# D1-Mini_Adapter_V4.net
KiCad netlist of a schematic drawn in EAGLE
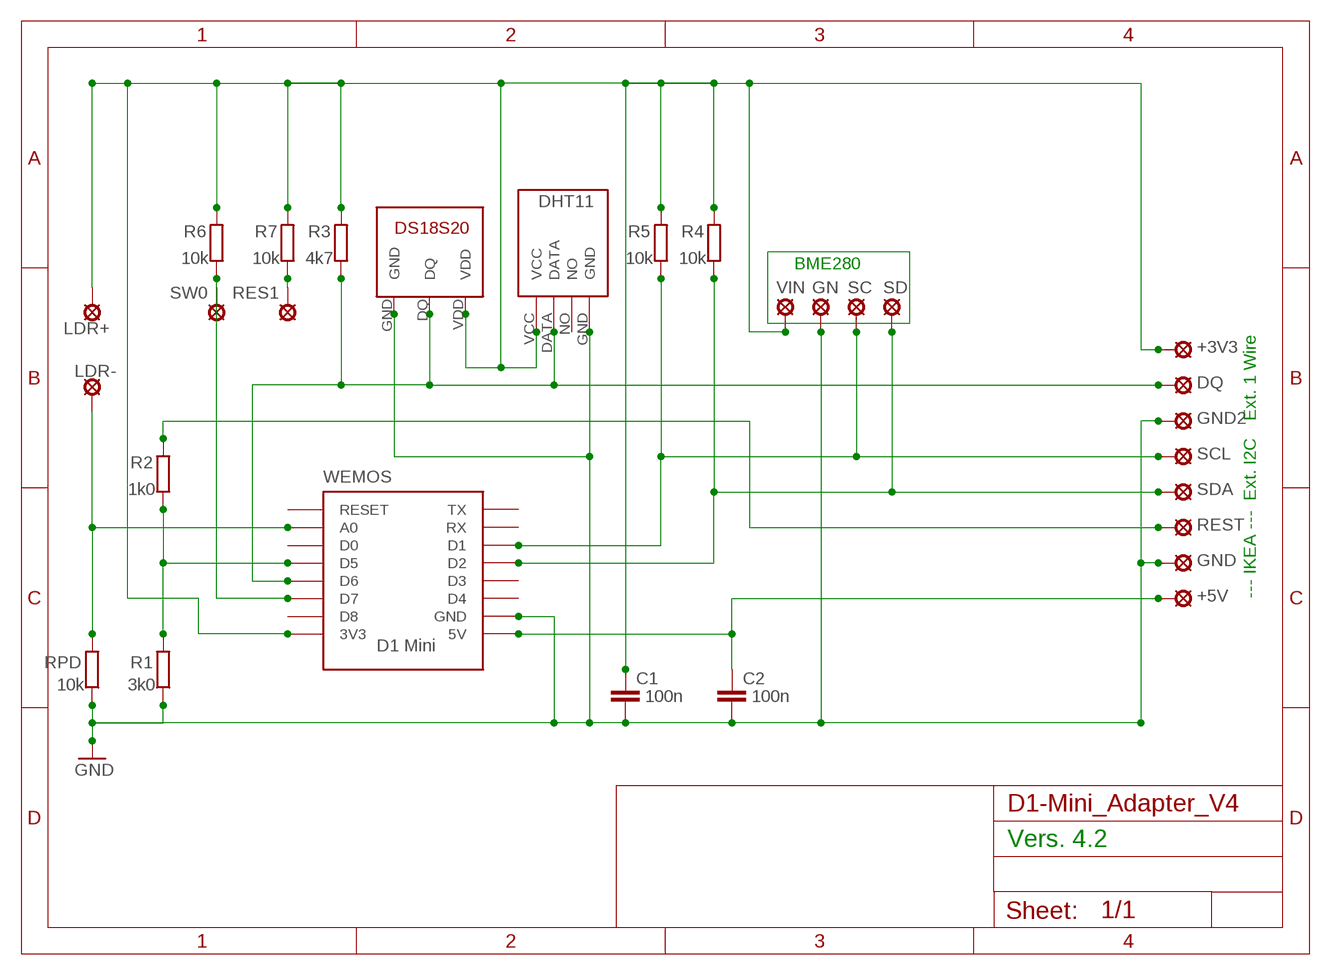
[diagram p0: schematic, sheet 1]

(export (version "E")
  (design (tool "Eeschema 10.0.6"))
  (components
    (comp (ref "+3V3")
      (value "SE13")
      (footprint "eagle-import:SE13")
      (libsource (lib "eagle-import") (part "SE13"))
    )
    (comp (ref "+5V")
      (value "SE13")
      (footprint "eagle-import:SE13")
      (libsource (lib "eagle-import") (part "SE13"))
    )
    (comp (ref "C1")
      (value "100n")
      (footprint "eagle-import:C025_050-045X075")
      (libsource (lib "eagle-import") (part "C-EU025_050-045X075"))
    )
    (comp (ref "C2")
      (value "100n")
      (footprint "eagle-import:C025_050-045X075")
      (libsource (lib "eagle-import") (part "C-EU025_050-045X075"))
    )
    (comp (ref "DQ")
      (value "SE13")
      (footprint "eagle-import:SE13")
      (libsource (lib "eagle-import") (part "SE13"))
    )
    (comp (ref "DS1820")
      (value "DS18S20")
      (footprint "eagle-import:DS18S20-PACKAGE")
      (libsource (lib "eagle-import") (part "DS18S20"))
    )
    (comp (ref "GN")
      (value "SE13")
      (footprint "eagle-import:SE13")
      (libsource (lib "eagle-import") (part "SE13"))
    )
    (comp (ref "GND")
      (value "SE13")
      (footprint "eagle-import:SE13")
      (libsource (lib "eagle-import") (part "SE13"))
    )
    (comp (ref "GND2")
      (value "SE13")
      (footprint "eagle-import:SE13")
      (libsource (lib "eagle-import") (part "SE13"))
    )
    (comp (ref "LDR+")
      (value "SE13")
      (footprint "eagle-import:SE13")
      (libsource (lib "eagle-import") (part "SE13"))
    )
    (comp (ref "LDR-")
      (value "SE13")
      (footprint "eagle-import:SE13")
      (libsource (lib "eagle-import") (part "SE13"))
    )
    (comp (ref "R1")
      (value "3k0")
      (footprint "eagle-import:0207_10")
      (libsource (lib "eagle-import") (part "R-EU_0207/10"))
    )
    (comp (ref "R2")
      (value "1k0")
      (footprint "eagle-import:0207_10")
      (libsource (lib "eagle-import") (part "R-EU_0207/10"))
    )
    (comp (ref "R3")
      (value "4k7")
      (footprint "eagle-import:0207_10")
      (libsource (lib "eagle-import") (part "R-EU_0207/10"))
    )
    (comp (ref "R4")
      (value "10k")
      (footprint "eagle-import:0207_10")
      (libsource (lib "eagle-import") (part "R-EU_0207/10"))
    )
    (comp (ref "R5")
      (value "10k")
      (footprint "eagle-import:0207_10")
      (libsource (lib "eagle-import") (part "R-EU_0207/10"))
    )
    (comp (ref "R6")
      (value "10k")
      (footprint "eagle-import:0207_10")
      (libsource (lib "eagle-import") (part "R-EU_0207/10"))
    )
    (comp (ref "R7")
      (value "10k")
      (footprint "eagle-import:0207_10")
      (libsource (lib "eagle-import") (part "R-EU_0207/10"))
    )
    (comp (ref "RES1")
      (value "SE13")
      (footprint "eagle-import:SE13")
      (libsource (lib "eagle-import") (part "SE13"))
    )
    (comp (ref "REST")
      (value "SE13")
      (footprint "eagle-import:SE13")
      (libsource (lib "eagle-import") (part "SE13"))
    )
    (comp (ref "RPD")
      (value "10k")
      (footprint "eagle-import:0207_10")
      (libsource (lib "eagle-import") (part "R-EU_0207/10"))
    )
    (comp (ref "SC")
      (value "SE13")
      (footprint "eagle-import:SE13")
      (libsource (lib "eagle-import") (part "SE13"))
    )
    (comp (ref "SCL")
      (value "SE13")
      (footprint "eagle-import:SE13")
      (libsource (lib "eagle-import") (part "SE13"))
    )
    (comp (ref "SD")
      (value "SE13")
      (footprint "eagle-import:SE13")
      (libsource (lib "eagle-import") (part "SE13"))
    )
    (comp (ref "SDA")
      (value "SE13")
      (footprint "eagle-import:SE13")
      (libsource (lib "eagle-import") (part "SE13"))
    )
    (comp (ref "SW0")
      (value "SE13")
      (footprint "eagle-import:SE13")
      (libsource (lib "eagle-import") (part "SE13"))
    )
    (comp (ref "U$1")
      (value "DHT11-PION.")
      (footprint "eagle-import:DHT11-PION.")
      (libsource (lib "eagle-import") (part "DHT11-PION."))
    )
    (comp (ref "VIN")
      (value "LSP13")
      (footprint "eagle-import:LSP13")
      (libsource (lib "eagle-import") (part "LSP13"))
    )
    (comp (ref "WEMOS")
      (value "D1 Mini")
      (footprint "eagle-import:WEMOS-D1-MINI")
      (libsource (lib "eagle-import") (part "WEMOS-D1-MINI"))
    )
  )
  (nets
    (net (code "1") (name "GND") (class "Default")
      (node (ref "C1") (pin "2") (pinfunction "2_2") (pintype "passive"))
      (node (ref "C2") (pin "2") (pinfunction "2_2") (pintype "passive"))
      (node (ref "DS1820") (pin "GND") (pinfunction "GND_GND") (pintype "power_in"))
      (node (ref "GN") (pin "MP") (pinfunction "MP_MP") (pintype "passive"))
      (node (ref "GND") (pin "MP") (pinfunction "MP_MP") (pintype "passive"))
      (node (ref "GND2") (pin "MP") (pinfunction "MP_MP") (pintype "passive"))
      (node (ref "R1") (pin "1") (pinfunction "1_1") (pintype "passive"))
      (node (ref "RPD") (pin "1") (pinfunction "1_1") (pintype "passive"))
      (node (ref "U$1") (pin "GND") (pinfunction "GND_GND") (pintype "bidirectional"))
      (node (ref "WEMOS") (pin "GND") (pinfunction "GND_GND") (pintype "bidirectional"))
    )
    (net (code "2") (name "Net-(+3V3-PadMP)") (class "Default")
      (node (ref "+3V3") (pin "MP") (pinfunction "MP_MP") (pintype "passive"))
      (node (ref "C1") (pin "1") (pinfunction "1_1") (pintype "passive"))
      (node (ref "DS1820") (pin "VDD") (pinfunction "VDD_VDD") (pintype "power_in"))
      (node (ref "LDR+") (pin "MP") (pinfunction "MP_MP") (pintype "passive"))
      (node (ref "R3") (pin "2") (pinfunction "2_2") (pintype "passive"))
      (node (ref "R4") (pin "2") (pinfunction "2_2") (pintype "passive"))
      (node (ref "R5") (pin "2") (pinfunction "2_2") (pintype "passive"))
      (node (ref "R6") (pin "2") (pinfunction "2_2") (pintype "passive"))
      (node (ref "R7") (pin "2") (pinfunction "2_2") (pintype "passive"))
      (node (ref "U$1") (pin "VCC") (pinfunction "VCC_VCC") (pintype "bidirectional"))
      (node (ref "VIN") (pin "MP") (pinfunction "MP_MP") (pintype "passive"))
      (node (ref "WEMOS") (pin "3V3") (pinfunction "3V3_3V3") (pintype "bidirectional"))
    )
    (net (code "3") (name "Net-(+5V-PadMP)") (class "Default")
      (node (ref "+5V") (pin "MP") (pinfunction "MP_MP") (pintype "passive"))
      (node (ref "C2") (pin "1") (pinfunction "1_1") (pintype "passive"))
      (node (ref "WEMOS") (pin "5V") (pinfunction "5V_5V") (pintype "bidirectional"))
    )
    (net (code "4") (name "Net-(DQ-PadMP)") (class "Default")
      (node (ref "DQ") (pin "MP") (pinfunction "MP_MP") (pintype "passive"))
      (node (ref "DS1820") (pin "DQ") (pinfunction "DQ_DQ") (pintype "bidirectional"))
      (node (ref "R3") (pin "1") (pinfunction "1_1") (pintype "passive"))
      (node (ref "U$1") (pin "DATA") (pinfunction "DATA_DATA") (pintype "bidirectional"))
      (node (ref "WEMOS") (pin "D6") (pinfunction "D6_D6") (pintype "bidirectional"))
    )
    (net (code "5") (name "Net-(LDR--PadMP)") (class "Default")
      (node (ref "LDR-") (pin "MP") (pinfunction "MP_MP") (pintype "passive"))
      (node (ref "RPD") (pin "2") (pinfunction "2_2") (pintype "passive"))
      (node (ref "WEMOS") (pin "A0") (pinfunction "A0_A0") (pintype "bidirectional"))
    )
    (net (code "6") (name "Net-(R1-Pad2)") (class "Default")
      (node (ref "R1") (pin "2") (pinfunction "2_2") (pintype "passive"))
      (node (ref "R2") (pin "1") (pinfunction "1_1") (pintype "passive"))
      (node (ref "WEMOS") (pin "D5") (pinfunction "D5_D5") (pintype "bidirectional"))
    )
    (net (code "7") (name "Net-(R2-Pad2)") (class "Default")
      (node (ref "R2") (pin "2") (pinfunction "2_2") (pintype "passive"))
      (node (ref "REST") (pin "MP") (pinfunction "MP_MP") (pintype "passive"))
    )
    (net (code "8") (name "Net-(R4-Pad1)") (class "Default")
      (node (ref "R4") (pin "1") (pinfunction "1_1") (pintype "passive"))
      (node (ref "SD") (pin "MP") (pinfunction "MP_MP") (pintype "passive"))
      (node (ref "SDA") (pin "MP") (pinfunction "MP_MP") (pintype "passive"))
      (node (ref "WEMOS") (pin "D2") (pinfunction "D2_D2") (pintype "bidirectional"))
    )
    (net (code "9") (name "Net-(R5-Pad1)") (class "Default")
      (node (ref "R5") (pin "1") (pinfunction "1_1") (pintype "passive"))
      (node (ref "SC") (pin "MP") (pinfunction "MP_MP") (pintype "passive"))
      (node (ref "SCL") (pin "MP") (pinfunction "MP_MP") (pintype "passive"))
      (node (ref "WEMOS") (pin "D1") (pinfunction "D1_D1") (pintype "bidirectional"))
    )
    (net (code "10") (name "Net-(R6-Pad1)") (class "Default")
      (node (ref "R6") (pin "1") (pinfunction "1_1") (pintype "passive"))
      (node (ref "SW0") (pin "MP") (pinfunction "MP_MP") (pintype "passive"))
      (node (ref "WEMOS") (pin "D7") (pinfunction "D7_D7") (pintype "bidirectional"))
    )
    (net (code "11") (name "Net-(R7-Pad1)") (class "Default")
      (node (ref "R7") (pin "1") (pinfunction "1_1") (pintype "passive"))
      (node (ref "RES1") (pin "MP") (pinfunction "MP_MP") (pintype "passive"))
    )
    (net (code "12") (name "unconnected-(U$1-PadNO)") (class "Default")
      (node (ref "U$1") (pin "NO") (pinfunction "NO_NO") (pintype "bidirectional"))
    )
    (net (code "13") (name "unconnected-(WEMOS-PadD0)") (class "Default")
      (node (ref "WEMOS") (pin "D0") (pinfunction "D0_D0") (pintype "bidirectional"))
    )
    (net (code "14") (name "unconnected-(WEMOS-PadD3)") (class "Default")
      (node (ref "WEMOS") (pin "D3") (pinfunction "D3_D3") (pintype "bidirectional"))
    )
    (net (code "15") (name "unconnected-(WEMOS-PadD4)") (class "Default")
      (node (ref "WEMOS") (pin "D4") (pinfunction "D4_D4") (pintype "bidirectional"))
    )
    (net (code "16") (name "unconnected-(WEMOS-PadD8)") (class "Default")
      (node (ref "WEMOS") (pin "D8") (pinfunction "D8_D8") (pintype "bidirectional"))
    )
    (net (code "17") (name "unconnected-(WEMOS-PadRESET)") (class "Default")
      (node (ref "WEMOS") (pin "RESET") (pinfunction "RESET_RESET") (pintype "bidirectional"))
    )
    (net (code "18") (name "unconnected-(WEMOS-PadRX)") (class "Default")
      (node (ref "WEMOS") (pin "RX") (pinfunction "RX_RX") (pintype "bidirectional"))
    )
    (net (code "19") (name "unconnected-(WEMOS-PadTX)") (class "Default")
      (node (ref "WEMOS") (pin "TX") (pinfunction "TX_TX") (pintype "bidirectional"))
    )
  )
)
